# Qwiic_RGB_Sensor_-_BH1749.net
KiCad netlist of a schematic drawn in EAGLE
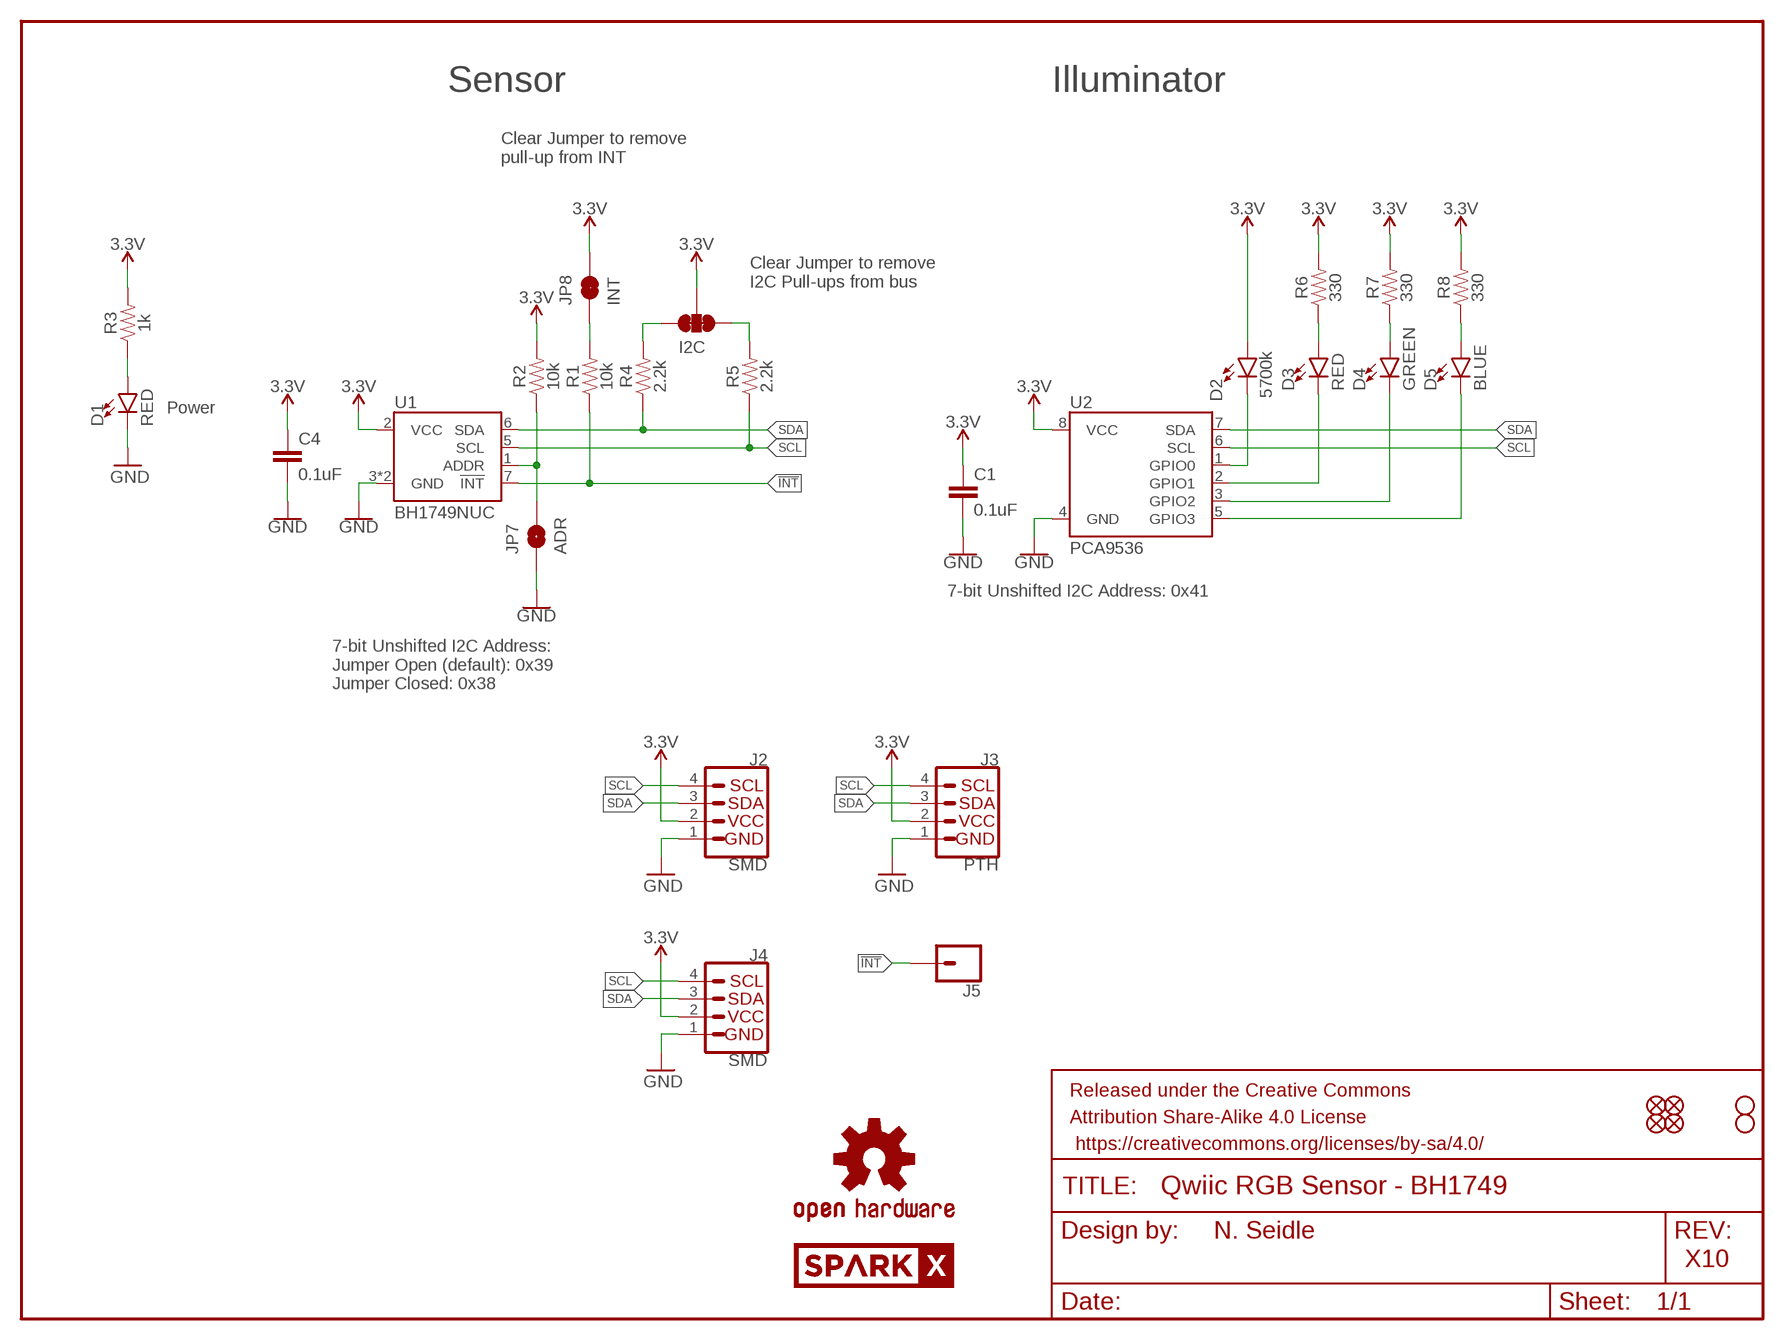
[diagram p0: schematic, sheet 1]

(export (version "E")
  (design (tool "Eeschema 10.0.6"))
  (components
    (comp (ref "C1")
      (value "0.1uF")
      (footprint "eagle-import:0603")
      (libsource (lib "eagle-import") (part "0.1UF-0603-25V-(+80/-20%)"))
    )
    (comp (ref "C4")
      (value "0.1uF")
      (footprint "eagle-import:0603")
      (libsource (lib "eagle-import") (part "0.1UF-0603-25V-(+80/-20%)"))
    )
    (comp (ref "D1")
      (value "RED")
      (footprint "eagle-import:LED-0603")
      (libsource (lib "eagle-import") (part "LED-RED0603"))
    )
    (comp (ref "D2")
      (value "5700k")
      (footprint "eagle-import:SUPER_BRIGHT_SMD_LED_1206")
      (libsource (lib "eagle-import") (part "LEDLD"))
    )
    (comp (ref "D3")
      (value "RED")
      (footprint "eagle-import:LED-0603")
      (libsource (lib "eagle-import") (part "LED-RED0603"))
    )
    (comp (ref "D4")
      (value "GREEN")
      (footprint "eagle-import:LED-0603")
      (libsource (lib "eagle-import") (part "LED-GREEN0603"))
    )
    (comp (ref "D5")
      (value "BLUE")
      (footprint "eagle-import:LED-0603")
      (libsource (lib "eagle-import") (part "LED-BLUE0603"))
    )
    (comp (ref "FRAME1")
      (value "FRAME-LETTER")
      (footprint "eagle-import:CREATIVE_COMMONS")
      (libsource (lib "eagle-import") (part "FRAME-LETTER"))
    )
    (comp (ref "I2C")
      (value "JUMPER-SMT_3_2-NC_TRACE_SILK")
      (footprint "eagle-import:SMT-JUMPER_3_2-NC_TRACE_SILK")
      (libsource (lib "eagle-import") (part "JUMPER-SMT_3_2-NC_TRACE_SILK"))
    )
    (comp (ref "J2")
      (value "SMD")
      (footprint "eagle-import:1X04_1MM_RA")
      (libsource (lib "eagle-import") (part "I2C_STANDARDJS-1MM"))
    )
    (comp (ref "J3")
      (value "PTH")
      (footprint "eagle-import:1X04_NO_SILK")
      (libsource (lib "eagle-import") (part "I2C_STANDARD_NO_SILK"))
    )
    (comp (ref "J4")
      (value "SMD")
      (footprint "eagle-import:1X04_1MM_RA")
      (libsource (lib "eagle-import") (part "I2C_STANDARDJS-1MM"))
    )
    (comp (ref "J5")
      (value "CONN_01PTH_NO_SILK_YES_STOP")
      (footprint "eagle-import:1X01_NO_SILK")
      (libsource (lib "eagle-import") (part "CONN_01PTH_NO_SILK_YES_STOP"))
    )
    (comp (ref "JP1")
      (value "FIDUCIALUFIDUCIAL")
      (footprint "eagle-import:MICRO-FIDUCIAL")
      (libsource (lib "eagle-import") (part "FIDUCIALUFIDUCIAL"))
    )
    (comp (ref "JP2")
      (value "FIDUCIALUFIDUCIAL")
      (footprint "eagle-import:MICRO-FIDUCIAL")
      (libsource (lib "eagle-import") (part "FIDUCIALUFIDUCIAL"))
    )
    (comp (ref "JP3")
      (value "STAND-OFF")
      (footprint "eagle-import:STAND-OFF")
      (libsource (lib "eagle-import") (part "STAND-OFF"))
    )
    (comp (ref "JP4")
      (value "STAND-OFF")
      (footprint "eagle-import:STAND-OFF")
      (libsource (lib "eagle-import") (part "STAND-OFF"))
    )
    (comp (ref "JP5")
      (value "FIDUCIALUFIDUCIAL")
      (footprint "eagle-import:MICRO-FIDUCIAL")
      (libsource (lib "eagle-import") (part "FIDUCIALUFIDUCIAL"))
    )
    (comp (ref "JP6")
      (value "FIDUCIALUFIDUCIAL")
      (footprint "eagle-import:MICRO-FIDUCIAL")
      (libsource (lib "eagle-import") (part "FIDUCIALUFIDUCIAL"))
    )
    (comp (ref "JP7")
      (value "ADR")
      (footprint "eagle-import:SMT-JUMPER_2_NO_SILK")
      (libsource (lib "eagle-import") (part "JUMPER-SMT_2_NO_SILK"))
    )
    (comp (ref "JP8")
      (value "INT")
      (footprint "eagle-import:SMT-JUMPER_2_NC_TRACE_SILK")
      (libsource (lib "eagle-import") (part "JUMPER-SMT_2_NC_TRACE_SILK"))
    )
    (comp (ref "LOGO1")
      (value "OSHW-LOGOMINI")
      (footprint "eagle-import:OSHW-LOGO-MINI")
      (libsource (lib "eagle-import") (part "OSHW-LOGOMINI"))
    )
    (comp (ref "R1")
      (value "10k")
      (footprint "eagle-import:0603")
      (libsource (lib "eagle-import") (part "10KOHM-0603-1/10W-1%"))
    )
    (comp (ref "R2")
      (value "10k")
      (footprint "eagle-import:0603")
      (libsource (lib "eagle-import") (part "10KOHM-0603-1/10W-1%"))
    )
    (comp (ref "R3")
      (value "1k")
      (footprint "eagle-import:0603")
      (libsource (lib "eagle-import") (part "1KOHM-0603-1/10W-1%"))
    )
    (comp (ref "R4")
      (value "2.2k")
      (footprint "eagle-import:0603")
      (libsource (lib "eagle-import") (part "2.2KOHM-0603-1/10W-1%"))
    )
    (comp (ref "R5")
      (value "2.2k")
      (footprint "eagle-import:0603")
      (libsource (lib "eagle-import") (part "2.2KOHM-0603-1/10W-1%"))
    )
    (comp (ref "R6")
      (value "330")
      (footprint "eagle-import:0603")
      (libsource (lib "eagle-import") (part "330OHM-0603-1/10W-1%"))
    )
    (comp (ref "R7")
      (value "330")
      (footprint "eagle-import:0603")
      (libsource (lib "eagle-import") (part "330OHM-0603-1/10W-1%"))
    )
    (comp (ref "R8")
      (value "330")
      (footprint "eagle-import:0603")
      (libsource (lib "eagle-import") (part "330OHM-0603-1/10W-1%"))
    )
    (comp (ref "U$1")
      (value "SPARKX-LOGO4")
      (footprint "eagle-import:SPARKX-MEDIUM")
      (libsource (lib "eagle-import") (part "SPARKX-LOGO4"))
    )
    (comp (ref "U$2")
      (value "SPARKX-LOGO4")
      (footprint "eagle-import:SPARKX-MEDIUM")
      (libsource (lib "eagle-import") (part "SPARKX-LOGO4"))
    )
    (comp (ref "U1")
      (value "BH1749NUC")
      (footprint "eagle-import:BH1749NUC")
      (libsource (lib "eagle-import") (part "BH1749NUC"))
    )
    (comp (ref "U2")
      (value "PCA9536")
      (footprint "eagle-import:MSOP8")
      (libsource (lib "eagle-import") (part "PCA9536"))
    )
  )
  (nets
    (net (code "1") (name "/~{INT}") (class "Default")
      (node (ref "J5") (pin "1") (pinfunction "1_1") (pintype "passive"))
      (node (ref "R1") (pin "1") (pinfunction "1_1") (pintype "passive"))
      (node (ref "U1") (pin "7") (pinfunction "~{INT}_7") (pintype "bidirectional"))
    )
    (net (code "2") (name "3.3V") (class "Default")
      (node (ref "C1") (pin "1") (pinfunction "1_1") (pintype "passive"))
      (node (ref "C4") (pin "1") (pinfunction "1_1") (pintype "passive"))
      (node (ref "D2") (pin "A") (pinfunction "A_A") (pintype "passive"))
      (node (ref "I2C") (pin "2") (pinfunction "2_2") (pintype "passive"))
      (node (ref "J2") (pin "2") (pinfunction "VCC_2") (pintype "power_in"))
      (node (ref "J3") (pin "2") (pinfunction "VCC_2") (pintype "power_in"))
      (node (ref "J4") (pin "2") (pinfunction "VCC_2") (pintype "power_in"))
      (node (ref "JP8") (pin "2") (pinfunction "2_2") (pintype "passive"))
      (node (ref "R2") (pin "2") (pinfunction "2_2") (pintype "passive"))
      (node (ref "R3") (pin "2") (pinfunction "2_2") (pintype "passive"))
      (node (ref "R6") (pin "2") (pinfunction "2_2") (pintype "passive"))
      (node (ref "R7") (pin "2") (pinfunction "2_2") (pintype "passive"))
      (node (ref "R8") (pin "2") (pinfunction "2_2") (pintype "passive"))
      (node (ref "U1") (pin "2") (pinfunction "VCC_2") (pintype "bidirectional"))
      (node (ref "U2") (pin "8") (pinfunction "VCC_8") (pintype "bidirectional"))
    )
    (net (code "3") (name "GND") (class "Default")
      (node (ref "C1") (pin "2") (pinfunction "2_2") (pintype "passive"))
      (node (ref "C4") (pin "2") (pinfunction "2_2") (pintype "passive"))
      (node (ref "D1") (pin "C") (pinfunction "C_C") (pintype "passive"))
      (node (ref "J2") (pin "1") (pinfunction "GND_1") (pintype "power_in"))
      (node (ref "J3") (pin "1") (pinfunction "GND_1") (pintype "power_in"))
      (node (ref "J4") (pin "1") (pinfunction "GND_1") (pintype "power_in"))
      (node (ref "JP7") (pin "1") (pinfunction "1_1") (pintype "passive"))
      (node (ref "U1") (pin "3") (pinfunction "GND_3") (pintype "bidirectional"))
      (node (ref "U1") (pin "4") (pinfunction "GND_4") (pintype "bidirectional"))
      (node (ref "U2") (pin "4") (pinfunction "GND_4") (pintype "bidirectional"))
    )
    (net (code "4") (name "Net-(D1-PadA)") (class "Default")
      (node (ref "D1") (pin "A") (pinfunction "A_A") (pintype "passive"))
      (node (ref "R3") (pin "1") (pinfunction "1_1") (pintype "passive"))
    )
    (net (code "5") (name "Net-(D3-PadA)") (class "Default")
      (node (ref "D3") (pin "A") (pinfunction "A_A") (pintype "passive"))
      (node (ref "R6") (pin "1") (pinfunction "1_1") (pintype "passive"))
    )
    (net (code "6") (name "Net-(D4-PadA)") (class "Default")
      (node (ref "D4") (pin "A") (pinfunction "A_A") (pintype "passive"))
      (node (ref "R7") (pin "1") (pinfunction "1_1") (pintype "passive"))
    )
    (net (code "7") (name "Net-(D5-PadA)") (class "Default")
      (node (ref "D5") (pin "A") (pinfunction "A_A") (pintype "passive"))
      (node (ref "R8") (pin "1") (pinfunction "1_1") (pintype "passive"))
    )
    (net (code "8") (name "Net-(I2C-Pad1)") (class "Default")
      (node (ref "I2C") (pin "1") (pinfunction "1_1") (pintype "passive"))
      (node (ref "R5") (pin "2") (pinfunction "2_2") (pintype "passive"))
    )
    (net (code "9") (name "Net-(I2C-Pad3)") (class "Default")
      (node (ref "I2C") (pin "3") (pinfunction "3_3") (pintype "passive"))
      (node (ref "R4") (pin "2") (pinfunction "2_2") (pintype "passive"))
    )
    (net (code "10") (name "Net-(JP8-Pad1)") (class "Default")
      (node (ref "JP8") (pin "1") (pinfunction "1_1") (pintype "passive"))
      (node (ref "R1") (pin "2") (pinfunction "2_2") (pintype "passive"))
    )
    (net (code "11") (name "Net-(U1-ADDR)") (class "Default")
      (node (ref "JP7") (pin "2") (pinfunction "2_2") (pintype "passive"))
      (node (ref "R2") (pin "1") (pinfunction "1_1") (pintype "passive"))
      (node (ref "U1") (pin "1") (pinfunction "ADDR_1") (pintype "bidirectional"))
    )
    (net (code "12") (name "Net-(U2-GPIO0)") (class "Default")
      (node (ref "D2") (pin "C") (pinfunction "C_C") (pintype "passive"))
      (node (ref "U2") (pin "1") (pinfunction "GPIO0_1") (pintype "bidirectional"))
    )
    (net (code "13") (name "Net-(U2-GPIO1)") (class "Default")
      (node (ref "D3") (pin "C") (pinfunction "C_C") (pintype "passive"))
      (node (ref "U2") (pin "2") (pinfunction "GPIO1_2") (pintype "bidirectional"))
    )
    (net (code "14") (name "Net-(U2-GPIO2)") (class "Default")
      (node (ref "D4") (pin "C") (pinfunction "C_C") (pintype "passive"))
      (node (ref "U2") (pin "3") (pinfunction "GPIO2_3") (pintype "bidirectional"))
    )
    (net (code "15") (name "Net-(U2-GPIO3)") (class "Default")
      (node (ref "D5") (pin "C") (pinfunction "C_C") (pintype "passive"))
      (node (ref "U2") (pin "5") (pinfunction "GPIO3_5") (pintype "bidirectional"))
    )
    (net (code "16") (name "SCL") (class "Default")
      (node (ref "J2") (pin "4") (pinfunction "SCL_4") (pintype "passive"))
      (node (ref "J3") (pin "4") (pinfunction "SCL_4") (pintype "passive"))
      (node (ref "J4") (pin "4") (pinfunction "SCL_4") (pintype "passive"))
      (node (ref "R5") (pin "1") (pinfunction "1_1") (pintype "passive"))
      (node (ref "U1") (pin "5") (pinfunction "SCL_5") (pintype "bidirectional"))
      (node (ref "U2") (pin "6") (pinfunction "SCL_6") (pintype "bidirectional"))
    )
    (net (code "17") (name "SDA") (class "Default")
      (node (ref "J2") (pin "3") (pinfunction "SDA_3") (pintype "passive"))
      (node (ref "J3") (pin "3") (pinfunction "SDA_3") (pintype "passive"))
      (node (ref "J4") (pin "3") (pinfunction "SDA_3") (pintype "passive"))
      (node (ref "R4") (pin "1") (pinfunction "1_1") (pintype "passive"))
      (node (ref "U1") (pin "6") (pinfunction "SDA_6") (pintype "bidirectional"))
      (node (ref "U2") (pin "7") (pinfunction "SDA_7") (pintype "bidirectional"))
    )
  )
)
